# LCD.net
KiCad netlist of a schematic drawn in EAGLE
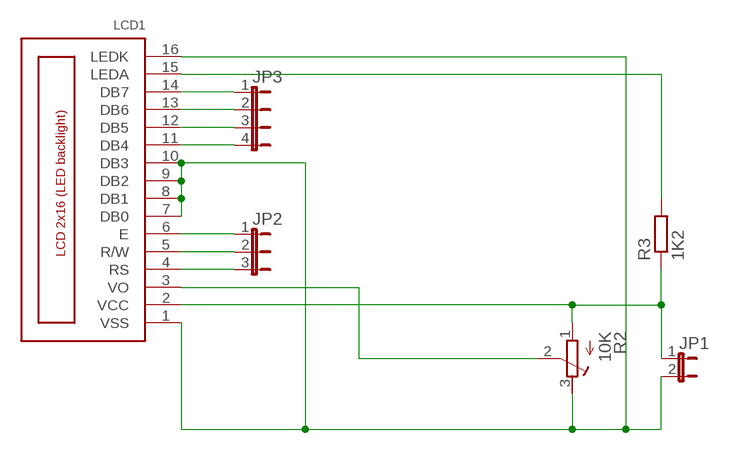
[diagram p0: schematic, sheet 1]

(export (version "E")
  (design (tool "Eeschema 10.0.6"))
  (components
    (comp (ref "JP1")
      (value "JP1E")
      (footprint "eagle-import:JP1")
      (libsource (lib "eagle-import") (part "JP1E"))
    )
    (comp (ref "JP2")
      (value "JP2E")
      (footprint "eagle-import:JP2")
      (libsource (lib "eagle-import") (part "JP2E"))
    )
    (comp (ref "JP3")
      (value "JP4E")
      (footprint "eagle-import:JP4")
      (libsource (lib "eagle-import") (part "JP4E"))
    )
    (comp (ref "LCD1")
      (value "LCD_2X16_SIL")
      (footprint "eagle-import:HY-1602F")
      (libsource (lib "eagle-import") (part "LCD_2X16_SIL"))
    )
    (comp (ref "R2")
      (value "10K")
      (footprint "eagle-import:RTRIM3339P")
      (libsource (lib "eagle-import") (part "R-TRIMM3339P"))
    )
    (comp (ref "R3")
      (value "1K2")
      (footprint "eagle-import:0207_10")
      (libsource (lib "eagle-import") (part "R-EU_0207/10"))
    )
  )
  (nets
    (net (code "1") (name "Net-(LCD1-DB0)") (class "Default")
      (node (ref "JP1") (pin "2") (pinfunction "2_2") (pintype "passive"))
      (node (ref "LCD1") (pin "1") (pinfunction "VSS_1") (pintype "power_in"))
      (node (ref "LCD1") (pin "10") (pinfunction "DB3_10") (pintype "bidirectional"))
      (node (ref "LCD1") (pin "16") (pinfunction "LEDK_16") (pintype "passive"))
      (node (ref "LCD1") (pin "7") (pinfunction "DB0_7") (pintype "bidirectional"))
      (node (ref "LCD1") (pin "8") (pinfunction "DB1_8") (pintype "bidirectional"))
      (node (ref "LCD1") (pin "9") (pinfunction "DB2_9") (pintype "bidirectional"))
      (node (ref "R2") (pin "3") (pinfunction "E_3") (pintype "passive"))
    )
    (net (code "2") (name "Net-(LCD1-DB4)") (class "Default")
      (node (ref "JP3") (pin "4") (pinfunction "4_4") (pintype "passive"))
      (node (ref "LCD1") (pin "11") (pinfunction "DB4_11") (pintype "bidirectional"))
    )
    (net (code "3") (name "Net-(LCD1-DB5)") (class "Default")
      (node (ref "JP3") (pin "3") (pinfunction "3_3") (pintype "passive"))
      (node (ref "LCD1") (pin "12") (pinfunction "DB5_12") (pintype "bidirectional"))
    )
    (net (code "4") (name "Net-(LCD1-DB6)") (class "Default")
      (node (ref "JP3") (pin "2") (pinfunction "2_2") (pintype "passive"))
      (node (ref "LCD1") (pin "13") (pinfunction "DB6_13") (pintype "bidirectional"))
    )
    (net (code "5") (name "Net-(LCD1-DB7)") (class "Default")
      (node (ref "JP3") (pin "1") (pinfunction "1_1") (pintype "passive"))
      (node (ref "LCD1") (pin "14") (pinfunction "DB7_14") (pintype "bidirectional"))
    )
    (net (code "6") (name "Net-(LCD1-E)") (class "Default")
      (node (ref "JP2") (pin "1") (pinfunction "1_1") (pintype "passive"))
      (node (ref "LCD1") (pin "6") (pinfunction "E_6") (pintype "input"))
    )
    (net (code "7") (name "Net-(LCD1-LEDA)") (class "Default")
      (node (ref "LCD1") (pin "15") (pinfunction "LEDA_15") (pintype "passive"))
      (node (ref "R3") (pin "2") (pinfunction "2_2") (pintype "passive"))
    )
    (net (code "8") (name "Net-(LCD1-RS)") (class "Default")
      (node (ref "JP2") (pin "3") (pinfunction "3_3") (pintype "passive"))
      (node (ref "LCD1") (pin "4") (pinfunction "RS_4") (pintype "input"))
    )
    (net (code "9") (name "Net-(LCD1-R{slash}W)") (class "Default")
      (node (ref "JP2") (pin "2") (pinfunction "2_2") (pintype "passive"))
      (node (ref "LCD1") (pin "5") (pinfunction "R/W_5") (pintype "input"))
    )
    (net (code "10") (name "Net-(LCD1-VCC)") (class "Default")
      (node (ref "JP1") (pin "1") (pinfunction "1_1") (pintype "passive"))
      (node (ref "LCD1") (pin "2") (pinfunction "VCC_2") (pintype "power_in"))
      (node (ref "R2") (pin "1") (pinfunction "A_1") (pintype "passive"))
      (node (ref "R3") (pin "1") (pinfunction "1_1") (pintype "passive"))
    )
    (net (code "11") (name "Net-(LCD1-VO)") (class "Default")
      (node (ref "LCD1") (pin "3") (pinfunction "VO_3") (pintype "input"))
      (node (ref "R2") (pin "2") (pinfunction "S_2") (pintype "passive"))
    )
  )
)
